# Nixie_clocks_Controls_board.net
KiCad netlist of a schematic drawn in Altium Designer
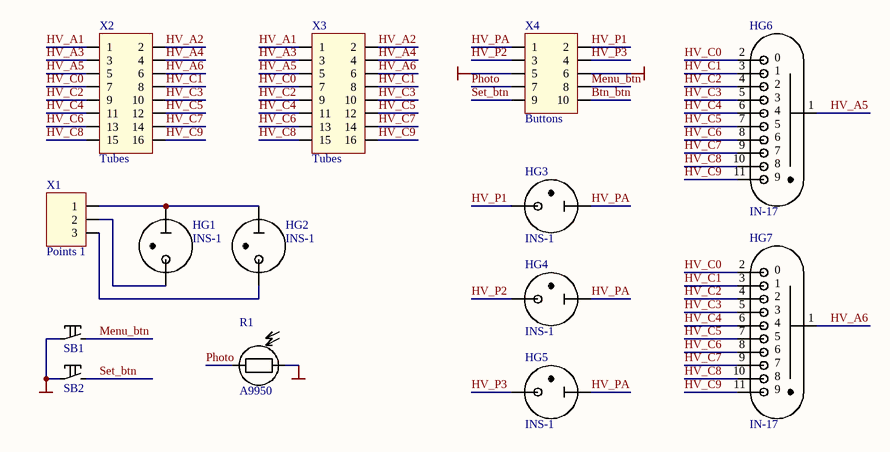
[diagram p0: Nixie_clocks_Controls_board.SchDoc]

(export (version "E")
  (design (tool "Eeschema 10.0.6"))
  (components
    (comp (ref "HG1")
      (value "INS-1")
      (footprint "INS-1")
      (description "INS-1 neon lamp verticap PCB mounting")
      (libsource (lib "Library") (part "Neon_lamp_polarized"))
    )
    (comp (ref "HG2")
      (value "INS-1")
      (footprint "INS-1")
      (description "INS-1 neon lamp verticap PCB mounting")
      (libsource (lib "Library") (part "Neon_lamp_polarized"))
    )
    (comp (ref "HG3")
      (value "INS-1")
      (footprint "INS-1")
      (description "INS-1 neon lamp verticap PCB mounting")
      (libsource (lib "Library") (part "Neon_lamp_polarized"))
    )
    (comp (ref "HG4")
      (value "INS-1")
      (footprint "INS-1")
      (description "INS-1 neon lamp verticap PCB mounting")
      (libsource (lib "Library") (part "Neon_lamp_polarized"))
    )
    (comp (ref "HG5")
      (value "INS-1")
      (footprint "INS-1")
      (description "INS-1 neon lamp verticap PCB mounting")
      (libsource (lib "Library") (part "Neon_lamp_polarized"))
    )
    (comp (ref "HG6")
      (value "IN-17")
      (footprint "IN-17_socket")
      (description "IN-17 PCB nixie tube")
      (libsource (lib "Library") (part "IN-17"))
    )
    (comp (ref "HG7")
      (value "IN-17")
      (footprint "IN-17_socket")
      (description "IN-17 PCB nixie tube")
      (libsource (lib "Library") (part "IN-17"))
    )
    (comp (ref "R1")
      (value "A9950")
      (footprint "A99")
      (description "THT 5mm photoresistor")
      (libsource (lib "Library") (part "Photoresistor"))
    )
    (comp (ref "SB1")
      (value "SPST_button")
      (footprint "TACT-69N-F")
      (description "Tact Button 6x6mm")
      (fields (field (name "PART NUMBER") "TACT-69N-F"))
      (libsource (lib "Library") (part "SPST_button"))
    )
    (comp (ref "SB2")
      (value "SPST_button")
      (footprint "TACT-69N-F")
      (description "Tact Button 6x6mm")
      (fields (field (name "PART NUMBER") "TACT-69N-F"))
      (libsource (lib "Library") (part "SPST_button"))
    )
    (comp (ref "X1")
      (value "Points 1")
      (footprint "WF-3")
      (description "PCB Connector")
      (fields (field (name "PART NUMBER") "WF-3"))
      (libsource (lib "Library") (part "Connector 3 pin"))
    )
    (comp (ref "X2")
      (value "Tubes")
      (footprint "IDC16")
      (description "PCB Connector")
      (fields (field (name "PART NUMBER") "IDC-16"))
      (libsource (lib "Library") (part "IDC16"))
    )
    (comp (ref "X3")
      (value "Tubes")
      (footprint "IDC16")
      (description "PCB Connector")
      (fields (field (name "PART NUMBER") "IDC-16"))
      (libsource (lib "Library") (part "IDC16"))
    )
    (comp (ref "X4")
      (value "Buttons")
      (footprint "IDC10")
      (description "PCB Connector")
      (fields (field (name "PART NUMBER") "IDC-10"))
      (libsource (lib "Library") (part "IDC10"))
    )
  )
  (nets
    (net (code "1") (name "/Btn_btn") (class "Default")
      (node (ref "X4") (pin "10") (pinfunction "10_10") (pintype "passive"))
    )
    (net (code "2") (name "/HV_A1") (class "Default")
      (node (ref "X2") (pin "1") (pinfunction "1_1") (pintype "passive"))
      (node (ref "X3") (pin "1") (pinfunction "1_1") (pintype "passive"))
    )
    (net (code "3") (name "/HV_A2") (class "Default")
      (node (ref "X2") (pin "2") (pinfunction "2_2") (pintype "passive"))
      (node (ref "X3") (pin "2") (pinfunction "2_2") (pintype "passive"))
    )
    (net (code "4") (name "/HV_A3") (class "Default")
      (node (ref "X2") (pin "3") (pinfunction "3_3") (pintype "passive"))
      (node (ref "X3") (pin "3") (pinfunction "3_3") (pintype "passive"))
    )
    (net (code "5") (name "/HV_A4") (class "Default")
      (node (ref "X2") (pin "4") (pinfunction "4_4") (pintype "passive"))
      (node (ref "X3") (pin "4") (pinfunction "4_4") (pintype "passive"))
    )
    (net (code "6") (name "/HV_A5") (class "Default")
      (node (ref "HG6") (pin "1") (pinfunction "A_1") (pintype "passive"))
      (node (ref "X2") (pin "5") (pinfunction "5_5") (pintype "passive"))
      (node (ref "X3") (pin "5") (pinfunction "5_5") (pintype "passive"))
    )
    (net (code "7") (name "/HV_A6") (class "Default")
      (node (ref "HG7") (pin "1") (pinfunction "A_1") (pintype "passive"))
      (node (ref "X2") (pin "6") (pinfunction "6_6") (pintype "passive"))
      (node (ref "X3") (pin "6") (pinfunction "6_6") (pintype "passive"))
    )
    (net (code "8") (name "/HV_C0") (class "Default")
      (node (ref "HG6") (pin "2") (pinfunction "0_2") (pintype "passive"))
      (node (ref "HG7") (pin "2") (pinfunction "0_2") (pintype "passive"))
      (node (ref "X2") (pin "7") (pinfunction "7_7") (pintype "passive"))
      (node (ref "X3") (pin "7") (pinfunction "7_7") (pintype "passive"))
    )
    (net (code "9") (name "/HV_C1") (class "Default")
      (node (ref "HG6") (pin "3") (pinfunction "1_3") (pintype "passive"))
      (node (ref "HG7") (pin "3") (pinfunction "1_3") (pintype "passive"))
      (node (ref "X2") (pin "8") (pinfunction "8_8") (pintype "passive"))
      (node (ref "X3") (pin "8") (pinfunction "8_8") (pintype "passive"))
    )
    (net (code "10") (name "/HV_C2") (class "Default")
      (node (ref "HG6") (pin "4") (pinfunction "2_4") (pintype "passive"))
      (node (ref "HG7") (pin "4") (pinfunction "2_4") (pintype "passive"))
      (node (ref "X2") (pin "9") (pinfunction "9_9") (pintype "passive"))
      (node (ref "X3") (pin "9") (pinfunction "9_9") (pintype "passive"))
    )
    (net (code "11") (name "/HV_C3") (class "Default")
      (node (ref "HG6") (pin "5") (pinfunction "3_5") (pintype "passive"))
      (node (ref "HG7") (pin "5") (pinfunction "3_5") (pintype "passive"))
      (node (ref "X2") (pin "10") (pinfunction "10_10") (pintype "passive"))
      (node (ref "X3") (pin "10") (pinfunction "10_10") (pintype "passive"))
    )
    (net (code "12") (name "/HV_C4") (class "Default")
      (node (ref "HG6") (pin "6") (pinfunction "4_6") (pintype "passive"))
      (node (ref "HG7") (pin "6") (pinfunction "4_6") (pintype "passive"))
      (node (ref "X2") (pin "11") (pinfunction "11_11") (pintype "passive"))
      (node (ref "X3") (pin "11") (pinfunction "11_11") (pintype "passive"))
    )
    (net (code "13") (name "/HV_C5") (class "Default")
      (node (ref "HG6") (pin "7") (pinfunction "5_7") (pintype "passive"))
      (node (ref "HG7") (pin "7") (pinfunction "5_7") (pintype "passive"))
      (node (ref "X2") (pin "12") (pinfunction "12_12") (pintype "passive"))
      (node (ref "X3") (pin "12") (pinfunction "12_12") (pintype "passive"))
    )
    (net (code "14") (name "/HV_C6") (class "Default")
      (node (ref "HG6") (pin "8") (pinfunction "6_8") (pintype "passive"))
      (node (ref "HG7") (pin "8") (pinfunction "6_8") (pintype "passive"))
      (node (ref "X2") (pin "13") (pinfunction "13_13") (pintype "passive"))
      (node (ref "X3") (pin "13") (pinfunction "13_13") (pintype "passive"))
    )
    (net (code "15") (name "/HV_C7") (class "Default")
      (node (ref "HG6") (pin "9") (pinfunction "7_9") (pintype "passive"))
      (node (ref "HG7") (pin "9") (pinfunction "7_9") (pintype "passive"))
      (node (ref "X2") (pin "14") (pinfunction "14_14") (pintype "passive"))
      (node (ref "X3") (pin "14") (pinfunction "14_14") (pintype "passive"))
    )
    (net (code "16") (name "/HV_C8") (class "Default")
      (node (ref "HG6") (pin "10") (pinfunction "8_10") (pintype "passive"))
      (node (ref "HG7") (pin "10") (pinfunction "8_10") (pintype "passive"))
      (node (ref "X2") (pin "15") (pinfunction "15_15") (pintype "passive"))
      (node (ref "X3") (pin "15") (pinfunction "15_15") (pintype "passive"))
    )
    (net (code "17") (name "/HV_C9") (class "Default")
      (node (ref "HG6") (pin "11") (pinfunction "9_11") (pintype "passive"))
      (node (ref "HG7") (pin "11") (pinfunction "9_11") (pintype "passive"))
      (node (ref "X2") (pin "16") (pinfunction "16_16") (pintype "passive"))
      (node (ref "X3") (pin "16") (pinfunction "16_16") (pintype "passive"))
    )
    (net (code "18") (name "/HV_P1") (class "Default")
      (node (ref "HG3") (pin "2") (pinfunction "2_2") (pintype "passive"))
      (node (ref "X4") (pin "2") (pinfunction "2_2") (pintype "passive"))
    )
    (net (code "19") (name "/HV_P2") (class "Default")
      (node (ref "HG4") (pin "2") (pinfunction "2_2") (pintype "passive"))
      (node (ref "X4") (pin "3") (pinfunction "3_3") (pintype "passive"))
    )
    (net (code "20") (name "/HV_P3") (class "Default")
      (node (ref "HG5") (pin "2") (pinfunction "2_2") (pintype "passive"))
      (node (ref "X4") (pin "4") (pinfunction "4_4") (pintype "passive"))
    )
    (net (code "21") (name "/HV_PA") (class "Default")
      (node (ref "HG3") (pin "1") (pinfunction "1_1") (pintype "passive"))
      (node (ref "HG4") (pin "1") (pinfunction "1_1") (pintype "passive"))
      (node (ref "HG5") (pin "1") (pinfunction "1_1") (pintype "passive"))
      (node (ref "X4") (pin "1") (pinfunction "1_1") (pintype "passive"))
    )
    (net (code "22") (name "/Menu_btn") (class "Default")
      (node (ref "SB1") (pin "2") (pinfunction "2_2") (pintype "passive"))
      (node (ref "X4") (pin "8") (pinfunction "8_8") (pintype "passive"))
    )
    (net (code "23") (name "/Photo") (class "Default")
      (node (ref "R1") (pin "1") (pinfunction "1_1") (pintype "passive"))
      (node (ref "X4") (pin "7") (pinfunction "7_7") (pintype "passive"))
    )
    (net (code "24") (name "/Set_btn") (class "Default")
      (node (ref "SB2") (pin "2") (pinfunction "2_2") (pintype "passive"))
      (node (ref "X4") (pin "9") (pinfunction "9_9") (pintype "passive"))
    )
    (net (code "25") (name "GND") (class "Default")
      (node (ref "R1") (pin "2") (pinfunction "2_2") (pintype "passive"))
      (node (ref "SB1") (pin "1") (pinfunction "1_1") (pintype "passive"))
      (node (ref "SB2") (pin "1") (pinfunction "1_1") (pintype "passive"))
      (node (ref "X4") (pin "5") (pinfunction "5_5") (pintype "passive"))
      (node (ref "X4") (pin "6") (pinfunction "6_6") (pintype "passive"))
    )
    (net (code "26") (name "Net-(HG1-Pad1)") (class "Default")
      (node (ref "HG1") (pin "1") (pinfunction "1_1") (pintype "passive"))
      (node (ref "HG2") (pin "1") (pinfunction "1_1") (pintype "passive"))
      (node (ref "X1") (pin "1") (pinfunction "1_1") (pintype "passive"))
    )
    (net (code "27") (name "Net-(HG1-Pad2)") (class "Default")
      (node (ref "HG1") (pin "2") (pinfunction "2_2") (pintype "passive"))
      (node (ref "X1") (pin "2") (pinfunction "2_2") (pintype "passive"))
    )
    (net (code "28") (name "Net-(HG2-Pad2)") (class "Default")
      (node (ref "HG2") (pin "2") (pinfunction "2_2") (pintype "passive"))
      (node (ref "X1") (pin "3") (pinfunction "3_3") (pintype "passive"))
    )
  )
)
